# PowerSupply.net
KiCad netlist of a schematic drawn in Altium Designer
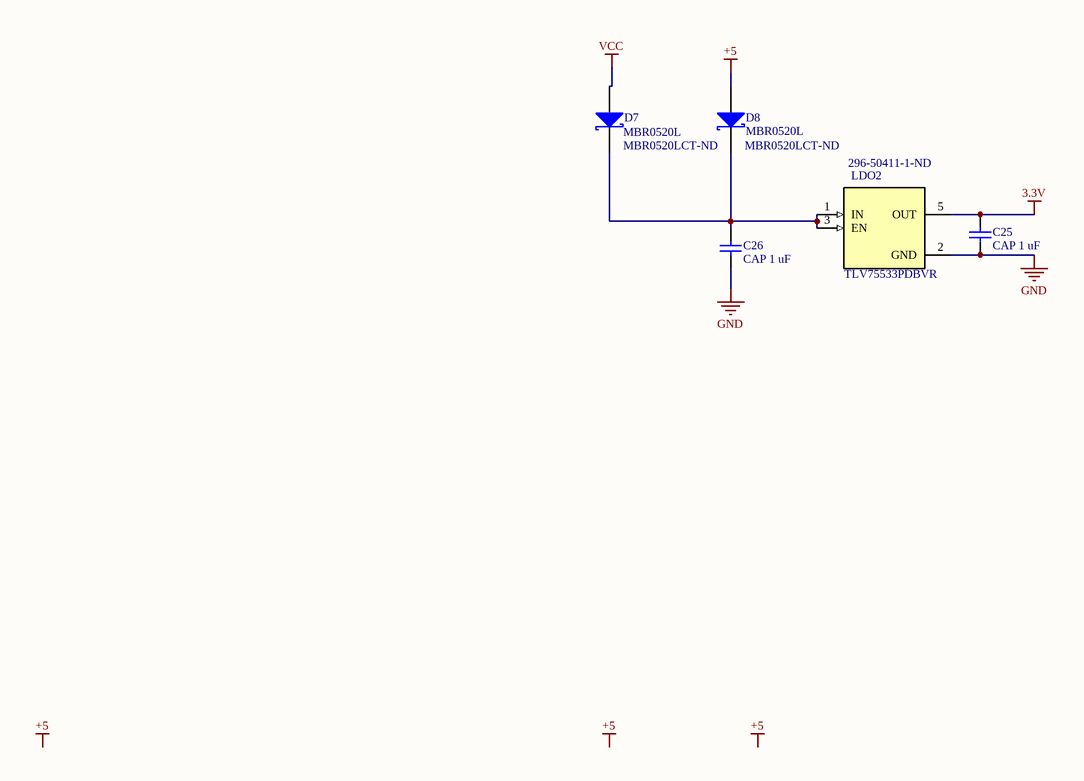
[diagram p0: PowerSupply.SchDoc]

(export (version "E")
  (design (tool "Eeschema 10.0.6"))
  (components
    (comp (ref "C25")
      (value "CAP 1 uF")
      (footprint "CL10A105KB8NNNC")
      (description "Capacitor")
      (fields (field (name "PUBLISHER") "Altium Limited"))
      (libsource (lib "Miscellaneous Devices") (part "Cap"))
    )
    (comp (ref "C26")
      (value "CAP 1 uF")
      (footprint "CL10A105KB8NNNC")
      (description "Capacitor")
      (fields (field (name "PUBLISHER") "Altium Limited"))
      (libsource (lib "Miscellaneous Devices") (part "Cap"))
    )
    (comp (ref "D7")
      (value "MBR0520L")
      (footprint "ON_Semi_CASE_425_0")
      (description "Schottky Diode")
      (fields
        (field (name "MANUFACTURER") "ON Semiconductor / Fairchild")
        (field (name "SUPPLIER PART NUMBER 1") "MBR0520LCT-ND")
      )
      (libsource (lib "MBR0520L") (part "MBR0520L"))
    )
    (comp (ref "D8")
      (value "MBR0520L")
      (footprint "ON_Semi_CASE_425_0")
      (description "Schottky Diode")
      (fields
        (field (name "MANUFACTURER") "ON Semiconductor / Fairchild")
        (field (name "SUPPLIER PART NUMBER 1") "MBR0520LCT-ND")
      )
      (libsource (lib "MBR0520L") (part "MBR0520L"))
    )
    (comp (ref "LDO2")
      (value "TLV75533PDBVR")
      (footprint "SOT95P280X145-5N")
      (description "500mA Low-IQ Small-Size Low-Dropout _LDO_ Regulator 5-SOT-23 -40 to 125")
      (fields
        (field (name "MF") "Texas Instruments")
        (field (name "SUPPLIER PART NUMBER 1") "296-50411-1-ND")
      )
      (libsource (lib "TLV75533PDBVR") (part "TLV75533PDBVR"))
    )
  )
  (nets
    (net (code "1") (name "+5") (class "Default")
      (node (ref "D8") (pin "1") (pinfunction "A_1") (pintype "passive"))
    )
    (net (code "2") (name "3.3V") (class "Default")
      (node (ref "C25") (pin "1") (pinfunction "1_1") (pintype "passive"))
      (node (ref "LDO2") (pin "5") (pinfunction "OUT_5") (pintype "power_in"))
    )
    (net (code "3") (name "GND") (class "Default")
      (node (ref "C25") (pin "2") (pinfunction "2_2") (pintype "passive"))
      (node (ref "C26") (pin "2") (pinfunction "2_2") (pintype "passive"))
      (node (ref "LDO2") (pin "2") (pinfunction "GND_2") (pintype "power_in"))
    )
    (net (code "4") (name "Net-(D7-K)") (class "Default")
      (node (ref "C26") (pin "1") (pinfunction "1_1") (pintype "passive"))
      (node (ref "D7") (pin "2") (pinfunction "K_2") (pintype "passive"))
      (node (ref "D8") (pin "2") (pinfunction "K_2") (pintype "passive"))
      (node (ref "LDO2") (pin "1") (pinfunction "IN_1") (pintype "input"))
      (node (ref "LDO2") (pin "3") (pinfunction "EN_3") (pintype "input"))
    )
    (net (code "5") (name "VCC") (class "Default")
      (node (ref "D7") (pin "1") (pinfunction "A_1") (pintype "passive"))
    )
  )
)
